# RAMPSDC.net
KiCad netlist of a schematic drawn in EAGLE
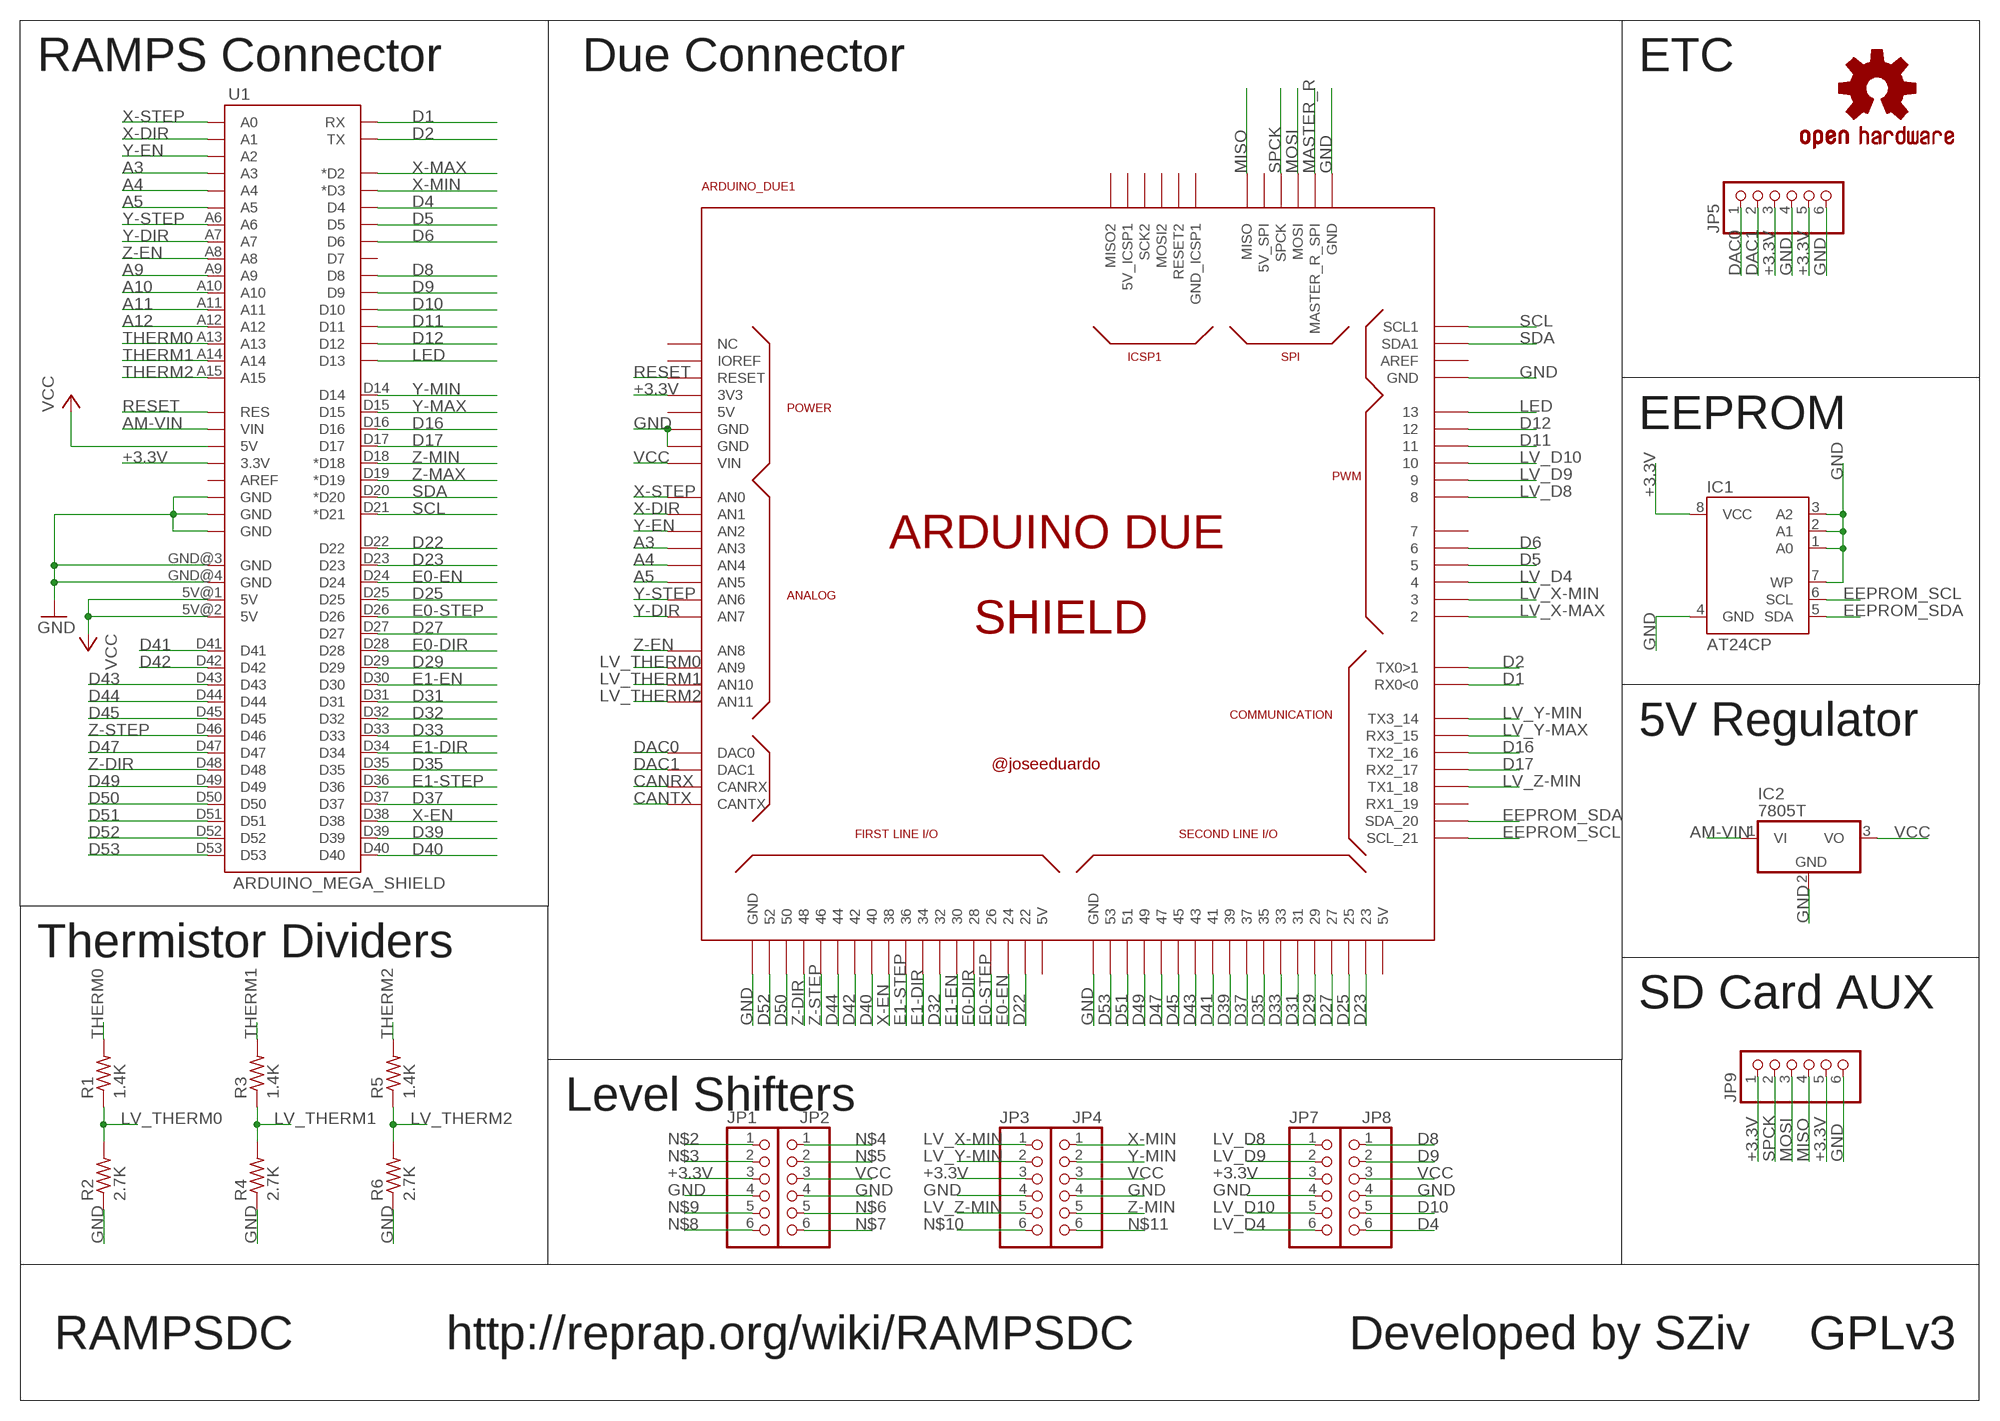
[diagram p0: schematic, sheet 1]

(export (version "E")
  (design (tool "Eeschema 10.0.6"))
  (components
    (comp (ref "ARDUINO_DUE1")
      (value "ARDUINO_DUE_SHIELD")
      (footprint "eagle-import:ARDUINO_DUE_SHIELD")
      (libsource (lib "eagle-import") (part "ARDUINO_DUE_SHIELD"))
    )
    (comp (ref "IC1")
      (value "AT24CP")
      (footprint "eagle-import:DIL08")
      (fields (field (name "MPN") "AT24C1024BW-SH-B"))
      (libsource (lib "eagle-import") (part "AT24CP"))
    )
    (comp (ref "IC2")
      (value "7805T")
      (footprint "eagle-import:TO220H")
      (libsource (lib "eagle-import") (part "78T05"))
    )
    (comp (ref "JP1")
      (value "PINHD-1X6")
      (footprint "eagle-import:1X06")
      (libsource (lib "eagle-import") (part "PINHD-1X6"))
    )
    (comp (ref "JP2")
      (value "PINHD-1X6")
      (footprint "eagle-import:1X06")
      (libsource (lib "eagle-import") (part "PINHD-1X6"))
    )
    (comp (ref "JP3")
      (value "PINHD-1X6")
      (footprint "eagle-import:1X06")
      (libsource (lib "eagle-import") (part "PINHD-1X6"))
    )
    (comp (ref "JP4")
      (value "PINHD-1X6")
      (footprint "eagle-import:1X06")
      (libsource (lib "eagle-import") (part "PINHD-1X6"))
    )
    (comp (ref "JP5")
      (value "PINHD-1X6")
      (footprint "eagle-import:1X06")
      (libsource (lib "eagle-import") (part "PINHD-1X6"))
    )
    (comp (ref "JP7")
      (value "PINHD-1X6")
      (footprint "eagle-import:1X06")
      (libsource (lib "eagle-import") (part "PINHD-1X6"))
    )
    (comp (ref "JP8")
      (value "PINHD-1X6")
      (footprint "eagle-import:1X06")
      (libsource (lib "eagle-import") (part "PINHD-1X6"))
    )
    (comp (ref "JP9")
      (value "PINHD-1X6")
      (footprint "eagle-import:1X06")
      (libsource (lib "eagle-import") (part "PINHD-1X6"))
    )
    (comp (ref "LOGO1")
      (value "OSHW-LOGOS")
      (footprint "eagle-import:OSHW-LOGO-S")
      (libsource (lib "eagle-import") (part "OSHW-LOGOS"))
    )
    (comp (ref "LOGO2")
      (value "OSHW-LOGOL-COPPER")
      (footprint "eagle-import:OSHW-LOGO-L_COPPER")
      (libsource (lib "eagle-import") (part "OSHW-LOGOL-COPPER"))
    )
    (comp (ref "R1")
      (value "1.4K")
      (footprint "eagle-import:R0805")
      (libsource (lib "eagle-import") (part "R-US_R0805"))
    )
    (comp (ref "R2")
      (value "2.7K")
      (footprint "eagle-import:R0805")
      (libsource (lib "eagle-import") (part "R-US_R0805"))
    )
    (comp (ref "R3")
      (value "1.4K")
      (footprint "eagle-import:R0805")
      (libsource (lib "eagle-import") (part "R-US_R0805"))
    )
    (comp (ref "R4")
      (value "2.7K")
      (footprint "eagle-import:R0805")
      (libsource (lib "eagle-import") (part "R-US_R0805"))
    )
    (comp (ref "R5")
      (value "1.4K")
      (footprint "eagle-import:R0805")
      (libsource (lib "eagle-import") (part "R-US_R0805"))
    )
    (comp (ref "R6")
      (value "2.7K")
      (footprint "eagle-import:R0805")
      (libsource (lib "eagle-import") (part "R-US_R0805"))
    )
    (comp (ref "U1")
      (value "ARDUINO_MEGA_SHIELD")
      (footprint "eagle-import:ARDUINO_MEGA_SHIELD")
      (libsource (lib "eagle-import") (part "ARDUINO_MEGA_SHIELD"))
    )
  )
  (nets
    (net (code "1") (name "/+3.3V") (class "Default")
      (node (ref "ARDUINO_DUE1") (pin "3V3") (pinfunction "3V3_3V3") (pintype "bidirectional"))
      (node (ref "IC1") (pin "8") (pinfunction "VCC_8") (pintype "power_in"))
      (node (ref "JP1") (pin "3") (pinfunction "3_3") (pintype "passive"))
      (node (ref "JP3") (pin "3") (pinfunction "3_3") (pintype "passive"))
      (node (ref "JP5") (pin "3") (pinfunction "3_3") (pintype "passive"))
      (node (ref "JP5") (pin "5") (pinfunction "5_5") (pintype "passive"))
      (node (ref "JP7") (pin "3") (pinfunction "3_3") (pintype "passive"))
      (node (ref "JP9") (pin "1") (pinfunction "1_1") (pintype "passive"))
      (node (ref "JP9") (pin "5") (pinfunction "5_5") (pintype "passive"))
      (node (ref "U1") (pin "3.3V") (pinfunction "3.3V_3.3V") (pintype "bidirectional"))
    )
    (net (code "2") (name "/A3") (class "Default")
      (node (ref "ARDUINO_DUE1") (pin "A3") (pinfunction "AN3_A3") (pintype "bidirectional"))
      (node (ref "U1") (pin "A3") (pinfunction "A3_A3") (pintype "bidirectional"))
    )
    (net (code "3") (name "/A4") (class "Default")
      (node (ref "ARDUINO_DUE1") (pin "A4") (pinfunction "AN4_A4") (pintype "bidirectional"))
      (node (ref "U1") (pin "A4") (pinfunction "A4_A4") (pintype "bidirectional"))
    )
    (net (code "4") (name "/A5") (class "Default")
      (node (ref "ARDUINO_DUE1") (pin "A5") (pinfunction "AN5_A5") (pintype "bidirectional"))
      (node (ref "U1") (pin "A5") (pinfunction "A5_A5") (pintype "bidirectional"))
    )
    (net (code "5") (name "/A9") (class "Default")
      (node (ref "U1") (pin "A9") (pinfunction "A9_A9") (pintype "bidirectional"))
    )
    (net (code "6") (name "/A10") (class "Default")
      (node (ref "U1") (pin "A10") (pinfunction "A10_A10") (pintype "bidirectional"))
    )
    (net (code "7") (name "/A11") (class "Default")
      (node (ref "U1") (pin "A11") (pinfunction "A11_A11") (pintype "bidirectional"))
    )
    (net (code "8") (name "/A12") (class "Default")
      (node (ref "U1") (pin "A12") (pinfunction "A12_A12") (pintype "bidirectional"))
    )
    (net (code "9") (name "/AM-VIN") (class "Default")
      (node (ref "IC2") (pin "1") (pinfunction "VI_1") (pintype "input"))
      (node (ref "U1") (pin "VIN") (pinfunction "VIN_VIN") (pintype "bidirectional"))
    )
    (net (code "10") (name "/CANRX") (class "Default")
      (node (ref "ARDUINO_DUE1") (pin "CANRX") (pinfunction "CANRX_CANRX") (pintype "bidirectional"))
    )
    (net (code "11") (name "/CANTX") (class "Default")
      (node (ref "ARDUINO_DUE1") (pin "CANTX") (pinfunction "CANTX_CANTX") (pintype "bidirectional"))
    )
    (net (code "12") (name "/D1") (class "Default")
      (node (ref "ARDUINO_DUE1") (pin "0") (pinfunction "RX0<0_0") (pintype "bidirectional"))
      (node (ref "U1") (pin "RX") (pinfunction "RX_RX") (pintype "bidirectional"))
    )
    (net (code "13") (name "/D2") (class "Default")
      (node (ref "ARDUINO_DUE1") (pin "1") (pinfunction "TX0>1_1") (pintype "bidirectional"))
      (node (ref "U1") (pin "TX") (pinfunction "TX_TX") (pintype "bidirectional"))
    )
    (net (code "14") (name "/D4") (class "Default")
      (node (ref "JP8") (pin "6") (pinfunction "6_6") (pintype "passive"))
      (node (ref "U1") (pin "D4") (pinfunction "D4_D4") (pintype "bidirectional"))
    )
    (net (code "15") (name "/D5") (class "Default")
      (node (ref "ARDUINO_DUE1") (pin "5") (pinfunction "5_5") (pintype "bidirectional"))
      (node (ref "U1") (pin "D5") (pinfunction "D5_D5") (pintype "bidirectional"))
    )
    (net (code "16") (name "/D6") (class "Default")
      (node (ref "ARDUINO_DUE1") (pin "6") (pinfunction "6_6") (pintype "bidirectional"))
      (node (ref "U1") (pin "D6") (pinfunction "D6_D6") (pintype "bidirectional"))
    )
    (net (code "17") (name "/D8") (class "Default")
      (node (ref "JP8") (pin "1") (pinfunction "1_1") (pintype "passive"))
      (node (ref "U1") (pin "D8") (pinfunction "D8_D8") (pintype "bidirectional"))
    )
    (net (code "18") (name "/D9") (class "Default")
      (node (ref "JP8") (pin "2") (pinfunction "2_2") (pintype "passive"))
      (node (ref "U1") (pin "D9") (pinfunction "D9_D9") (pintype "bidirectional"))
    )
    (net (code "19") (name "/D10") (class "Default")
      (node (ref "JP8") (pin "5") (pinfunction "5_5") (pintype "passive"))
      (node (ref "U1") (pin "D10") (pinfunction "D10_D10") (pintype "bidirectional"))
    )
    (net (code "20") (name "/D11") (class "Default")
      (node (ref "ARDUINO_DUE1") (pin "11") (pinfunction "11_11") (pintype "bidirectional"))
      (node (ref "U1") (pin "D11") (pinfunction "D11_D11") (pintype "bidirectional"))
    )
    (net (code "21") (name "/D12") (class "Default")
      (node (ref "ARDUINO_DUE1") (pin "12") (pinfunction "12_12") (pintype "bidirectional"))
      (node (ref "U1") (pin "D12") (pinfunction "D12_D12") (pintype "bidirectional"))
    )
    (net (code "22") (name "/D16") (class "Default")
      (node (ref "ARDUINO_DUE1") (pin "16") (pinfunction "TX2_16_16") (pintype "bidirectional"))
      (node (ref "U1") (pin "D16") (pinfunction "D16_D16") (pintype "bidirectional"))
    )
    (net (code "23") (name "/D17") (class "Default")
      (node (ref "ARDUINO_DUE1") (pin "17") (pinfunction "RX2_17_17") (pintype "bidirectional"))
      (node (ref "U1") (pin "D17") (pinfunction "D17_D17") (pintype "bidirectional"))
    )
    (net (code "24") (name "/D22") (class "Default")
      (node (ref "ARDUINO_DUE1") (pin "22") (pinfunction "22_22") (pintype "bidirectional"))
      (node (ref "U1") (pin "D22") (pinfunction "D22_D22") (pintype "bidirectional"))
    )
    (net (code "25") (name "/D23") (class "Default")
      (node (ref "ARDUINO_DUE1") (pin "23") (pinfunction "23_23") (pintype "bidirectional"))
      (node (ref "U1") (pin "D23") (pinfunction "D23_D23") (pintype "bidirectional"))
    )
    (net (code "26") (name "/D25") (class "Default")
      (node (ref "ARDUINO_DUE1") (pin "25") (pinfunction "25_25") (pintype "bidirectional"))
      (node (ref "U1") (pin "D25") (pinfunction "D25_D25") (pintype "bidirectional"))
    )
    (net (code "27") (name "/D27") (class "Default")
      (node (ref "ARDUINO_DUE1") (pin "27") (pinfunction "27_27") (pintype "bidirectional"))
      (node (ref "U1") (pin "D27") (pinfunction "D27_D27") (pintype "bidirectional"))
    )
    (net (code "28") (name "/D29") (class "Default")
      (node (ref "ARDUINO_DUE1") (pin "29") (pinfunction "29_29") (pintype "bidirectional"))
      (node (ref "U1") (pin "D29") (pinfunction "D29_D29") (pintype "bidirectional"))
    )
    (net (code "29") (name "/D31") (class "Default")
      (node (ref "ARDUINO_DUE1") (pin "31") (pinfunction "31_31") (pintype "bidirectional"))
      (node (ref "U1") (pin "D31") (pinfunction "D31_D31") (pintype "bidirectional"))
    )
    (net (code "30") (name "/D32") (class "Default")
      (node (ref "ARDUINO_DUE1") (pin "32") (pinfunction "32_32") (pintype "bidirectional"))
      (node (ref "U1") (pin "D32") (pinfunction "D32_D32") (pintype "bidirectional"))
    )
    (net (code "31") (name "/D33") (class "Default")
      (node (ref "ARDUINO_DUE1") (pin "33") (pinfunction "33_33") (pintype "bidirectional"))
      (node (ref "U1") (pin "D33") (pinfunction "D33_D33") (pintype "bidirectional"))
    )
    (net (code "32") (name "/D35") (class "Default")
      (node (ref "ARDUINO_DUE1") (pin "35") (pinfunction "35_35") (pintype "bidirectional"))
      (node (ref "U1") (pin "D35") (pinfunction "D35_D35") (pintype "bidirectional"))
    )
    (net (code "33") (name "/D37") (class "Default")
      (node (ref "ARDUINO_DUE1") (pin "37") (pinfunction "37_37") (pintype "bidirectional"))
      (node (ref "U1") (pin "D37") (pinfunction "D37_D37") (pintype "bidirectional"))
    )
    (net (code "34") (name "/D39") (class "Default")
      (node (ref "ARDUINO_DUE1") (pin "39") (pinfunction "39_39") (pintype "bidirectional"))
      (node (ref "U1") (pin "D39") (pinfunction "D39_D39") (pintype "bidirectional"))
    )
    (net (code "35") (name "/D40") (class "Default")
      (node (ref "ARDUINO_DUE1") (pin "40") (pinfunction "40_40") (pintype "bidirectional"))
      (node (ref "U1") (pin "D40") (pinfunction "D40_D40") (pintype "bidirectional"))
    )
    (net (code "36") (name "/D41") (class "Default")
      (node (ref "ARDUINO_DUE1") (pin "41") (pinfunction "41_41") (pintype "bidirectional"))
      (node (ref "U1") (pin "D41") (pinfunction "D41_D41") (pintype "bidirectional"))
    )
    (net (code "37") (name "/D42") (class "Default")
      (node (ref "ARDUINO_DUE1") (pin "42") (pinfunction "42_42") (pintype "bidirectional"))
      (node (ref "U1") (pin "D42") (pinfunction "D42_D42") (pintype "bidirectional"))
    )
    (net (code "38") (name "/D43") (class "Default")
      (node (ref "ARDUINO_DUE1") (pin "43") (pinfunction "43_43") (pintype "bidirectional"))
      (node (ref "U1") (pin "D43") (pinfunction "D43_D43") (pintype "bidirectional"))
    )
    (net (code "39") (name "/D44") (class "Default")
      (node (ref "ARDUINO_DUE1") (pin "44") (pinfunction "44_44") (pintype "bidirectional"))
      (node (ref "U1") (pin "D44") (pinfunction "D44_D44") (pintype "bidirectional"))
    )
    (net (code "40") (name "/D45") (class "Default")
      (node (ref "ARDUINO_DUE1") (pin "45") (pinfunction "45_45") (pintype "bidirectional"))
      (node (ref "U1") (pin "D45") (pinfunction "D45_D45") (pintype "bidirectional"))
    )
    (net (code "41") (name "/D47") (class "Default")
      (node (ref "ARDUINO_DUE1") (pin "47") (pinfunction "47_47") (pintype "bidirectional"))
      (node (ref "U1") (pin "D47") (pinfunction "D47_D47") (pintype "bidirectional"))
    )
    (net (code "42") (name "/D49") (class "Default")
      (node (ref "ARDUINO_DUE1") (pin "49") (pinfunction "49_49") (pintype "bidirectional"))
      (node (ref "U1") (pin "D49") (pinfunction "D49_D49") (pintype "bidirectional"))
    )
    (net (code "43") (name "/D50") (class "Default")
      (node (ref "ARDUINO_DUE1") (pin "50") (pinfunction "50_50") (pintype "bidirectional"))
      (node (ref "U1") (pin "D50") (pinfunction "D50_D50") (pintype "bidirectional"))
    )
    (net (code "44") (name "/D51") (class "Default")
      (node (ref "ARDUINO_DUE1") (pin "51") (pinfunction "51_51") (pintype "bidirectional"))
      (node (ref "U1") (pin "D51") (pinfunction "D51_D51") (pintype "bidirectional"))
    )
    (net (code "45") (name "/D52") (class "Default")
      (node (ref "ARDUINO_DUE1") (pin "52") (pinfunction "52_52") (pintype "bidirectional"))
      (node (ref "U1") (pin "D52") (pinfunction "D52_D52") (pintype "bidirectional"))
    )
    (net (code "46") (name "/D53") (class "Default")
      (node (ref "ARDUINO_DUE1") (pin "53") (pinfunction "53_53") (pintype "bidirectional"))
      (node (ref "U1") (pin "D53") (pinfunction "D53_D53") (pintype "bidirectional"))
    )
    (net (code "47") (name "/DAC0") (class "Default")
      (node (ref "ARDUINO_DUE1") (pin "DAC0") (pinfunction "DAC0_DAC0") (pintype "bidirectional"))
      (node (ref "JP5") (pin "1") (pinfunction "1_1") (pintype "passive"))
    )
    (net (code "48") (name "/DAC1") (class "Default")
      (node (ref "ARDUINO_DUE1") (pin "DAC1") (pinfunction "DAC1_DAC1") (pintype "bidirectional"))
      (node (ref "JP5") (pin "2") (pinfunction "2_2") (pintype "passive"))
    )
    (net (code "49") (name "/E0-DIR") (class "Default")
      (node (ref "ARDUINO_DUE1") (pin "28") (pinfunction "28_28") (pintype "bidirectional"))
      (node (ref "U1") (pin "D28") (pinfunction "D28_D28") (pintype "bidirectional"))
    )
    (net (code "50") (name "/E0-EN") (class "Default")
      (node (ref "ARDUINO_DUE1") (pin "24") (pinfunction "24_24") (pintype "bidirectional"))
      (node (ref "U1") (pin "D24") (pinfunction "D24_D24") (pintype "bidirectional"))
    )
    (net (code "51") (name "/E0-STEP") (class "Default")
      (node (ref "ARDUINO_DUE1") (pin "26") (pinfunction "26_26") (pintype "bidirectional"))
      (node (ref "U1") (pin "D26") (pinfunction "D26_D26") (pintype "bidirectional"))
    )
    (net (code "52") (name "/E1-DIR") (class "Default")
      (node (ref "ARDUINO_DUE1") (pin "34") (pinfunction "34_34") (pintype "bidirectional"))
      (node (ref "U1") (pin "D34") (pinfunction "D34_D34") (pintype "bidirectional"))
    )
    (net (code "53") (name "/E1-EN") (class "Default")
      (node (ref "ARDUINO_DUE1") (pin "30") (pinfunction "30_30") (pintype "bidirectional"))
      (node (ref "U1") (pin "D30") (pinfunction "D30_D30") (pintype "bidirectional"))
    )
    (net (code "54") (name "/E1-STEP") (class "Default")
      (node (ref "ARDUINO_DUE1") (pin "36") (pinfunction "36_36") (pintype "bidirectional"))
      (node (ref "U1") (pin "D36") (pinfunction "D36_D36") (pintype "bidirectional"))
    )
    (net (code "55") (name "/EEPROM_SCL") (class "Default")
      (node (ref "ARDUINO_DUE1") (pin "21") (pinfunction "SCL_21_21") (pintype "bidirectional"))
      (node (ref "IC1") (pin "6") (pinfunction "SCL_6") (pintype "bidirectional"))
    )
    (net (code "56") (name "/EEPROM_SDA") (class "Default")
      (node (ref "ARDUINO_DUE1") (pin "20") (pinfunction "SDA_20_20") (pintype "bidirectional"))
      (node (ref "IC1") (pin "5") (pinfunction "SDA_5") (pintype "bidirectional"))
    )
    (net (code "57") (name "/LED") (class "Default")
      (node (ref "ARDUINO_DUE1") (pin "13") (pinfunction "13_13") (pintype "bidirectional"))
      (node (ref "U1") (pin "D13") (pinfunction "D13_D13") (pintype "bidirectional"))
    )
    (net (code "58") (name "/LV_D4") (class "Default")
      (node (ref "ARDUINO_DUE1") (pin "4") (pinfunction "4_4") (pintype "bidirectional"))
      (node (ref "JP7") (pin "6") (pinfunction "6_6") (pintype "passive"))
    )
    (net (code "59") (name "/LV_D8") (class "Default")
      (node (ref "ARDUINO_DUE1") (pin "8") (pinfunction "8_8") (pintype "bidirectional"))
      (node (ref "JP7") (pin "1") (pinfunction "1_1") (pintype "passive"))
    )
    (net (code "60") (name "/LV_D9") (class "Default")
      (node (ref "ARDUINO_DUE1") (pin "9") (pinfunction "9_9") (pintype "bidirectional"))
      (node (ref "JP7") (pin "2") (pinfunction "2_2") (pintype "passive"))
    )
    (net (code "61") (name "/LV_D10") (class "Default")
      (node (ref "ARDUINO_DUE1") (pin "10") (pinfunction "10_10") (pintype "bidirectional"))
      (node (ref "JP7") (pin "5") (pinfunction "5_5") (pintype "passive"))
    )
    (net (code "62") (name "/LV_THERM0") (class "Default")
      (node (ref "ARDUINO_DUE1") (pin "A9") (pinfunction "AN9_A9") (pintype "bidirectional"))
      (node (ref "R1") (pin "1") (pinfunction "1_1") (pintype "passive"))
      (node (ref "R2") (pin "2") (pinfunction "2_2") (pintype "passive"))
    )
    (net (code "63") (name "/LV_THERM1") (class "Default")
      (node (ref "ARDUINO_DUE1") (pin "A10") (pinfunction "AN10_A10") (pintype "bidirectional"))
      (node (ref "R3") (pin "1") (pinfunction "1_1") (pintype "passive"))
      (node (ref "R4") (pin "2") (pinfunction "2_2") (pintype "passive"))
    )
    (net (code "64") (name "/LV_THERM2") (class "Default")
      (node (ref "ARDUINO_DUE1") (pin "A11") (pinfunction "AN11_A11") (pintype "bidirectional"))
      (node (ref "R5") (pin "1") (pinfunction "1_1") (pintype "passive"))
      (node (ref "R6") (pin "2") (pinfunction "2_2") (pintype "passive"))
    )
    (net (code "65") (name "/LV_X-MAX") (class "Default")
      (node (ref "ARDUINO_DUE1") (pin "2") (pinfunction "2_2") (pintype "bidirectional"))
    )
    (net (code "66") (name "/LV_X-MIN") (class "Default")
      (node (ref "ARDUINO_DUE1") (pin "3") (pinfunction "3_3") (pintype "bidirectional"))
      (node (ref "JP3") (pin "1") (pinfunction "1_1") (pintype "passive"))
    )
    (net (code "67") (name "/LV_Y-MAX") (class "Default")
      (node (ref "ARDUINO_DUE1") (pin "15") (pinfunction "RX3_15_15") (pintype "bidirectional"))
    )
    (net (code "68") (name "/LV_Y-MIN") (class "Default")
      (node (ref "ARDUINO_DUE1") (pin "14") (pinfunction "TX3_14_14") (pintype "bidirectional"))
      (node (ref "JP3") (pin "2") (pinfunction "2_2") (pintype "passive"))
    )
    (net (code "69") (name "/LV_Z-MIN") (class "Default")
      (node (ref "ARDUINO_DUE1") (pin "18") (pinfunction "TX1_18_18") (pintype "bidirectional"))
      (node (ref "JP3") (pin "5") (pinfunction "5_5") (pintype "passive"))
    )
    (net (code "70") (name "/MASTER_R") (class "Default")
      (node (ref "ARDUINO_DUE1") (pin "MASTER_RESET_SPI") (pinfunction "MASTER_R_SPI_MASTER_RESET_SPI") (pintype "bidirectional"))
    )
    (net (code "71") (name "/MISO") (class "Default")
      (node (ref "ARDUINO_DUE1") (pin "MISO") (pinfunction "MISO_MISO") (pintype "bidirectional"))
      (node (ref "JP9") (pin "4") (pinfunction "4_4") (pintype "passive"))
    )
    (net (code "72") (name "/MOSI") (class "Default")
      (node (ref "ARDUINO_DUE1") (pin "MOSI") (pinfunction "MOSI_MOSI") (pintype "bidirectional"))
      (node (ref "JP9") (pin "3") (pinfunction "3_3") (pintype "passive"))
    )
    (net (code "73") (name "/N$2") (class "Default")
      (node (ref "JP1") (pin "1") (pinfunction "1_1") (pintype "passive"))
    )
    (net (code "74") (name "/N$3") (class "Default")
      (node (ref "JP1") (pin "2") (pinfunction "2_2") (pintype "passive"))
    )
    (net (code "75") (name "/N$4") (class "Default")
      (node (ref "JP2") (pin "1") (pinfunction "1_1") (pintype "passive"))
    )
    (net (code "76") (name "/N$5") (class "Default")
      (node (ref "JP2") (pin "2") (pinfunction "2_2") (pintype "passive"))
    )
    (net (code "77") (name "/N$6") (class "Default")
      (node (ref "JP2") (pin "5") (pinfunction "5_5") (pintype "passive"))
    )
    (net (code "78") (name "/N$7") (class "Default")
      (node (ref "JP2") (pin "6") (pinfunction "6_6") (pintype "passive"))
    )
    (net (code "79") (name "/N$8") (class "Default")
      (node (ref "JP1") (pin "6") (pinfunction "6_6") (pintype "passive"))
    )
    (net (code "80") (name "/N$9") (class "Default")
      (node (ref "JP1") (pin "5") (pinfunction "5_5") (pintype "passive"))
    )
    (net (code "81") (name "/N$10") (class "Default")
      (node (ref "JP3") (pin "6") (pinfunction "6_6") (pintype "passive"))
    )
    (net (code "82") (name "/N$11") (class "Default")
      (node (ref "JP4") (pin "6") (pinfunction "6_6") (pintype "passive"))
    )
    (net (code "83") (name "/RESET") (class "Default")
      (node (ref "ARDUINO_DUE1") (pin "RESET") (pinfunction "RESET_RESET") (pintype "bidirectional"))
      (node (ref "U1") (pin "RES") (pinfunction "RES_RES") (pintype "bidirectional"))
    )
    (net (code "84") (name "/SCL") (class "Default")
      (node (ref "ARDUINO_DUE1") (pin "SCL1") (pinfunction "SCL1_SCL1") (pintype "bidirectional"))
      (node (ref "U1") (pin "D21") (pinfunction "*D21_D21") (pintype "bidirectional"))
    )
    (net (code "85") (name "/SDA") (class "Default")
      (node (ref "ARDUINO_DUE1") (pin "SDA1") (pinfunction "SDA1_SDA1") (pintype "bidirectional"))
      (node (ref "U1") (pin "D20") (pinfunction "*D20_D20") (pintype "bidirectional"))
    )
    (net (code "86") (name "/SPCK") (class "Default")
      (node (ref "ARDUINO_DUE1") (pin "SPCK") (pinfunction "SPCK_SPCK") (pintype "bidirectional"))
      (node (ref "JP9") (pin "2") (pinfunction "2_2") (pintype "passive"))
    )
    (net (code "87") (name "/THERM0") (class "Default")
      (node (ref "R1") (pin "2") (pinfunction "2_2") (pintype "passive"))
      (node (ref "U1") (pin "A13") (pinfunction "A13_A13") (pintype "bidirectional"))
    )
    (net (code "88") (name "/THERM1") (class "Default")
      (node (ref "R3") (pin "2") (pinfunction "2_2") (pintype "passive"))
      (node (ref "U1") (pin "A14") (pinfunction "A14_A14") (pintype "bidirectional"))
    )
    (net (code "89") (name "/THERM2") (class "Default")
      (node (ref "R5") (pin "2") (pinfunction "2_2") (pintype "passive"))
      (node (ref "U1") (pin "A15") (pinfunction "A15_A15") (pintype "bidirectional"))
    )
    (net (code "90") (name "/X-DIR") (class "Default")
      (node (ref "ARDUINO_DUE1") (pin "A1") (pinfunction "AN1_A1") (pintype "bidirectional"))
      (node (ref "U1") (pin "A1") (pinfunction "A1_A1") (pintype "bidirectional"))
    )
    (net (code "91") (name "/X-EN") (class "Default")
      (node (ref "ARDUINO_DUE1") (pin "38") (pinfunction "38_38") (pintype "bidirectional"))
      (node (ref "U1") (pin "D38") (pinfunction "D38_D38") (pintype "bidirectional"))
    )
    (net (code "92") (name "/X-MAX") (class "Default")
      (node (ref "U1") (pin "D2") (pinfunction "*D2_D2") (pintype "bidirectional"))
    )
    (net (code "93") (name "/X-MIN") (class "Default")
      (node (ref "JP4") (pin "1") (pinfunction "1_1") (pintype "passive"))
      (node (ref "U1") (pin "D3") (pinfunction "*D3_D3") (pintype "bidirectional"))
    )
    (net (code "94") (name "/X-STEP") (class "Default")
      (node (ref "ARDUINO_DUE1") (pin "A0") (pinfunction "AN0_A0") (pintype "bidirectional"))
      (node (ref "U1") (pin "A0") (pinfunction "A0_A0") (pintype "bidirectional"))
    )
    (net (code "95") (name "/Y-DIR") (class "Default")
      (node (ref "ARDUINO_DUE1") (pin "A7") (pinfunction "AN7_A7") (pintype "bidirectional"))
      (node (ref "U1") (pin "A7") (pinfunction "A7_A7") (pintype "bidirectional"))
    )
    (net (code "96") (name "/Y-EN") (class "Default")
      (node (ref "ARDUINO_DUE1") (pin "A2") (pinfunction "AN2_A2") (pintype "bidirectional"))
      (node (ref "U1") (pin "A2") (pinfunction "A2_A2") (pintype "bidirectional"))
    )
    (net (code "97") (name "/Y-MAX") (class "Default")
      (node (ref "U1") (pin "D15") (pinfunction "D15_D15") (pintype "bidirectional"))
    )
    (net (code "98") (name "/Y-MIN") (class "Default")
      (node (ref "JP4") (pin "2") (pinfunction "2_2") (pintype "passive"))
      (node (ref "U1") (pin "D14") (pinfunction "D14_D14") (pintype "bidirectional"))
    )
    (net (code "99") (name "/Y-STEP") (class "Default")
      (node (ref "ARDUINO_DUE1") (pin "A6") (pinfunction "AN6_A6") (pintype "bidirectional"))
      (node (ref "U1") (pin "A6") (pinfunction "A6_A6") (pintype "bidirectional"))
    )
    (net (code "100") (name "/Z-DIR") (class "Default")
      (node (ref "ARDUINO_DUE1") (pin "48") (pinfunction "48_48") (pintype "bidirectional"))
      (node (ref "U1") (pin "D48") (pinfunction "D48_D48") (pintype "bidirectional"))
    )
    (net (code "101") (name "/Z-EN") (class "Default")
      (node (ref "ARDUINO_DUE1") (pin "A8") (pinfunction "AN8_A8") (pintype "bidirectional"))
      (node (ref "U1") (pin "A8") (pinfunction "A8_A8") (pintype "bidirectional"))
    )
    (net (code "102") (name "/Z-MAX") (class "Default")
      (node (ref "U1") (pin "D19") (pinfunction "*D19_D19") (pintype "bidirectional"))
    )
    (net (code "103") (name "/Z-MIN") (class "Default")
      (node (ref "JP4") (pin "5") (pinfunction "5_5") (pintype "passive"))
      (node (ref "U1") (pin "D18") (pinfunction "*D18_D18") (pintype "bidirectional"))
    )
    (net (code "104") (name "/Z-STEP") (class "Default")
      (node (ref "ARDUINO_DUE1") (pin "46") (pinfunction "46_46") (pintype "bidirectional"))
      (node (ref "U1") (pin "D46") (pinfunction "D46_D46") (pintype "bidirectional"))
    )
    (net (code "105") (name "GND") (class "Default")
      (node (ref "ARDUINO_DUE1") (pin "GND") (pinfunction "GND_GND") (pintype "bidirectional"))
      (node (ref "ARDUINO_DUE1") (pin "GND_1") (pinfunction "GND_GND_1") (pintype "bidirectional"))
      (node (ref "ARDUINO_DUE1") (pin "GND_2") (pinfunction "GND_GND_2") (pintype "bidirectional"))
      (node (ref "ARDUINO_DUE1") (pin "GND_3") (pinfunction "GND_GND_3") (pintype "bidirectional"))
      (node (ref "ARDUINO_DUE1") (pin "GND_4") (pinfunction "GND_GND_4") (pintype "bidirectional"))
      (node (ref "ARDUINO_DUE1") (pin "GND_5") (pinfunction "GND_GND_5") (pintype "bidirectional"))
      (node (ref "IC1") (pin "1") (pinfunction "A0_1") (pintype "input"))
      (node (ref "IC1") (pin "2") (pinfunction "A1_2") (pintype "input"))
      (node (ref "IC1") (pin "3") (pinfunction "A2_3") (pintype "input"))
      (node (ref "IC1") (pin "4") (pinfunction "GND_4") (pintype "power_in"))
      (node (ref "IC1") (pin "7") (pinfunction "WP_7") (pintype "input"))
      (node (ref "IC2") (pin "2") (pinfunction "GND_2") (pintype "passive"))
      (node (ref "JP1") (pin "4") (pinfunction "4_4") (pintype "passive"))
      (node (ref "JP2") (pin "4") (pinfunction "4_4") (pintype "passive"))
      (node (ref "JP3") (pin "4") (pinfunction "4_4") (pintype "passive"))
      (node (ref "JP4") (pin "4") (pinfunction "4_4") (pintype "passive"))
      (node (ref "JP5") (pin "4") (pinfunction "4_4") (pintype "passive"))
      (node (ref "JP5") (pin "6") (pinfunction "6_6") (pintype "passive"))
      (node (ref "JP7") (pin "4") (pinfunction "4_4") (pintype "passive"))
      (node (ref "JP8") (pin "4") (pinfunction "4_4") (pintype "passive"))
      (node (ref "JP9") (pin "6") (pinfunction "6_6") (pintype "passive"))
      (node (ref "R2") (pin "1") (pinfunction "1_1") (pintype "passive"))
      (node (ref "R4") (pin "1") (pinfunction "1_1") (pintype "passive"))
      (node (ref "R6") (pin "1") (pinfunction "1_1") (pintype "passive"))
      (node (ref "U1") (pin "GND@0") (pinfunction "GND_GND@0") (pintype "power_in"))
      (node (ref "U1") (pin "GND@1") (pinfunction "GND_GND@1") (pintype "power_in"))
      (node (ref "U1") (pin "GND@2") (pinfunction "GND_GND@2") (pintype "power_in"))
      (node (ref "U1") (pin "GND@3") (pinfunction "GND_GND@3") (pintype "power_in"))
      (node (ref "U1") (pin "GND@4") (pinfunction "GND_GND@4") (pintype "power_in"))
    )
    (net (code "106") (name "VCC") (class "Default")
      (node (ref "ARDUINO_DUE1") (pin "VIN") (pinfunction "VIN_VIN") (pintype "bidirectional"))
      (node (ref "IC2") (pin "3") (pinfunction "VO_3") (pintype "passive"))
      (node (ref "JP2") (pin "3") (pinfunction "3_3") (pintype "passive"))
      (node (ref "JP4") (pin "3") (pinfunction "3_3") (pintype "passive"))
      (node (ref "JP8") (pin "3") (pinfunction "3_3") (pintype "passive"))
      (node (ref "U1") (pin "5V@0") (pinfunction "5V_5V@0") (pintype "power_in"))
      (node (ref "U1") (pin "5V@1") (pinfunction "5V_5V@1") (pintype "power_in"))
      (node (ref "U1") (pin "5V@2") (pinfunction "5V_5V@2") (pintype "power_in"))
    )
    (net (code "107") (name "unconnected-(ARDUINO_DUE1-5V-Pad5V0)") (class "Default")
      (node (ref "ARDUINO_DUE1") (pin "5V0") (pinfunction "5V_5V0") (pintype "bidirectional"))
    )
    (net (code "108") (name "unconnected-(ARDUINO_DUE1-5V-Pad5V0_1)") (class "Default")
      (node (ref "ARDUINO_DUE1") (pin "5V0_1") (pinfunction "5V_5V0_1") (pintype "bidirectional"))
    )
    (net (code "109") (name "unconnected-(ARDUINO_DUE1-5V-Pad5V0_2)") (class "Default")
      (node (ref "ARDUINO_DUE1") (pin "5V0_2") (pinfunction "5V_5V0_2") (pintype "bidirectional"))
    )
    (net (code "110") (name "unconnected-(ARDUINO_DUE1-5V_SPI-Pad5V_2)") (class "Default")
      (node (ref "ARDUINO_DUE1") (pin "5V_2") (pinfunction "5V_SPI_5V_2") (pintype "bidirectional"))
    )
    (net (code "111") (name "unconnected-(ARDUINO_DUE1-NC-PadNC_2)") (class "Default")
      (node (ref "ARDUINO_DUE1") (pin "NC_2") (pinfunction "NC_NC_2") (pintype "no_connect"))
    )
    (net (code "112") (name "unconnected-(ARDUINO_DUE1-Pad5V_ICSP1)") (class "Default")
      (node (ref "ARDUINO_DUE1") (pin "5V_ICSP1") (pinfunction "5V_ICSP1_5V_ICSP1") (pintype "bidirectional"))
    )
    (net (code "113") (name "unconnected-(ARDUINO_DUE1-Pad7)") (class "Default")
      (node (ref "ARDUINO_DUE1") (pin "7") (pinfunction "7_7") (pintype "bidirectional"))
    )
    (net (code "114") (name "unconnected-(ARDUINO_DUE1-PadAREF)") (class "Default")
      (node (ref "ARDUINO_DUE1") (pin "AREF") (pinfunction "AREF_AREF") (pintype "bidirectional"))
    )
    (net (code "115") (name "unconnected-(ARDUINO_DUE1-PadGND_ICSP1)") (class "Default")
      (node (ref "ARDUINO_DUE1") (pin "GND_ICSP1") (pinfunction "GND_ICSP1_GND_ICSP1") (pintype "bidirectional"))
    )
    (net (code "116") (name "unconnected-(ARDUINO_DUE1-PadIOREF)") (class "Default")
      (node (ref "ARDUINO_DUE1") (pin "IOREF") (pinfunction "IOREF_IOREF") (pintype "bidirectional"))
    )
    (net (code "117") (name "unconnected-(ARDUINO_DUE1-PadMISO2)") (class "Default")
      (node (ref "ARDUINO_DUE1") (pin "MISO2") (pinfunction "MISO2_MISO2") (pintype "bidirectional"))
    )
    (net (code "118") (name "unconnected-(ARDUINO_DUE1-PadMOSI2)") (class "Default")
      (node (ref "ARDUINO_DUE1") (pin "MOSI2") (pinfunction "MOSI2_MOSI2") (pintype "bidirectional"))
    )
    (net (code "119") (name "unconnected-(ARDUINO_DUE1-PadRESET2)") (class "Default")
      (node (ref "ARDUINO_DUE1") (pin "RESET2") (pinfunction "RESET2_RESET2") (pintype "bidirectional"))
    )
    (net (code "120") (name "unconnected-(ARDUINO_DUE1-PadSCK2)") (class "Default")
      (node (ref "ARDUINO_DUE1") (pin "SCK2") (pinfunction "SCK2_SCK2") (pintype "bidirectional"))
    )
    (net (code "121") (name "unconnected-(ARDUINO_DUE1-RX1_19-Pad19)") (class "Default")
      (node (ref "ARDUINO_DUE1") (pin "19") (pinfunction "RX1_19_19") (pintype "bidirectional"))
    )
    (net (code "122") (name "unconnected-(U1-PadAREF)") (class "Default")
      (node (ref "U1") (pin "AREF") (pinfunction "AREF_AREF") (pintype "bidirectional"))
    )
    (net (code "123") (name "unconnected-(U1-PadD7)") (class "Default")
      (node (ref "U1") (pin "D7") (pinfunction "D7_D7") (pintype "bidirectional"))
    )
  )
)
